# M135A.net
KiCad netlist of a schematic drawn in EAGLE
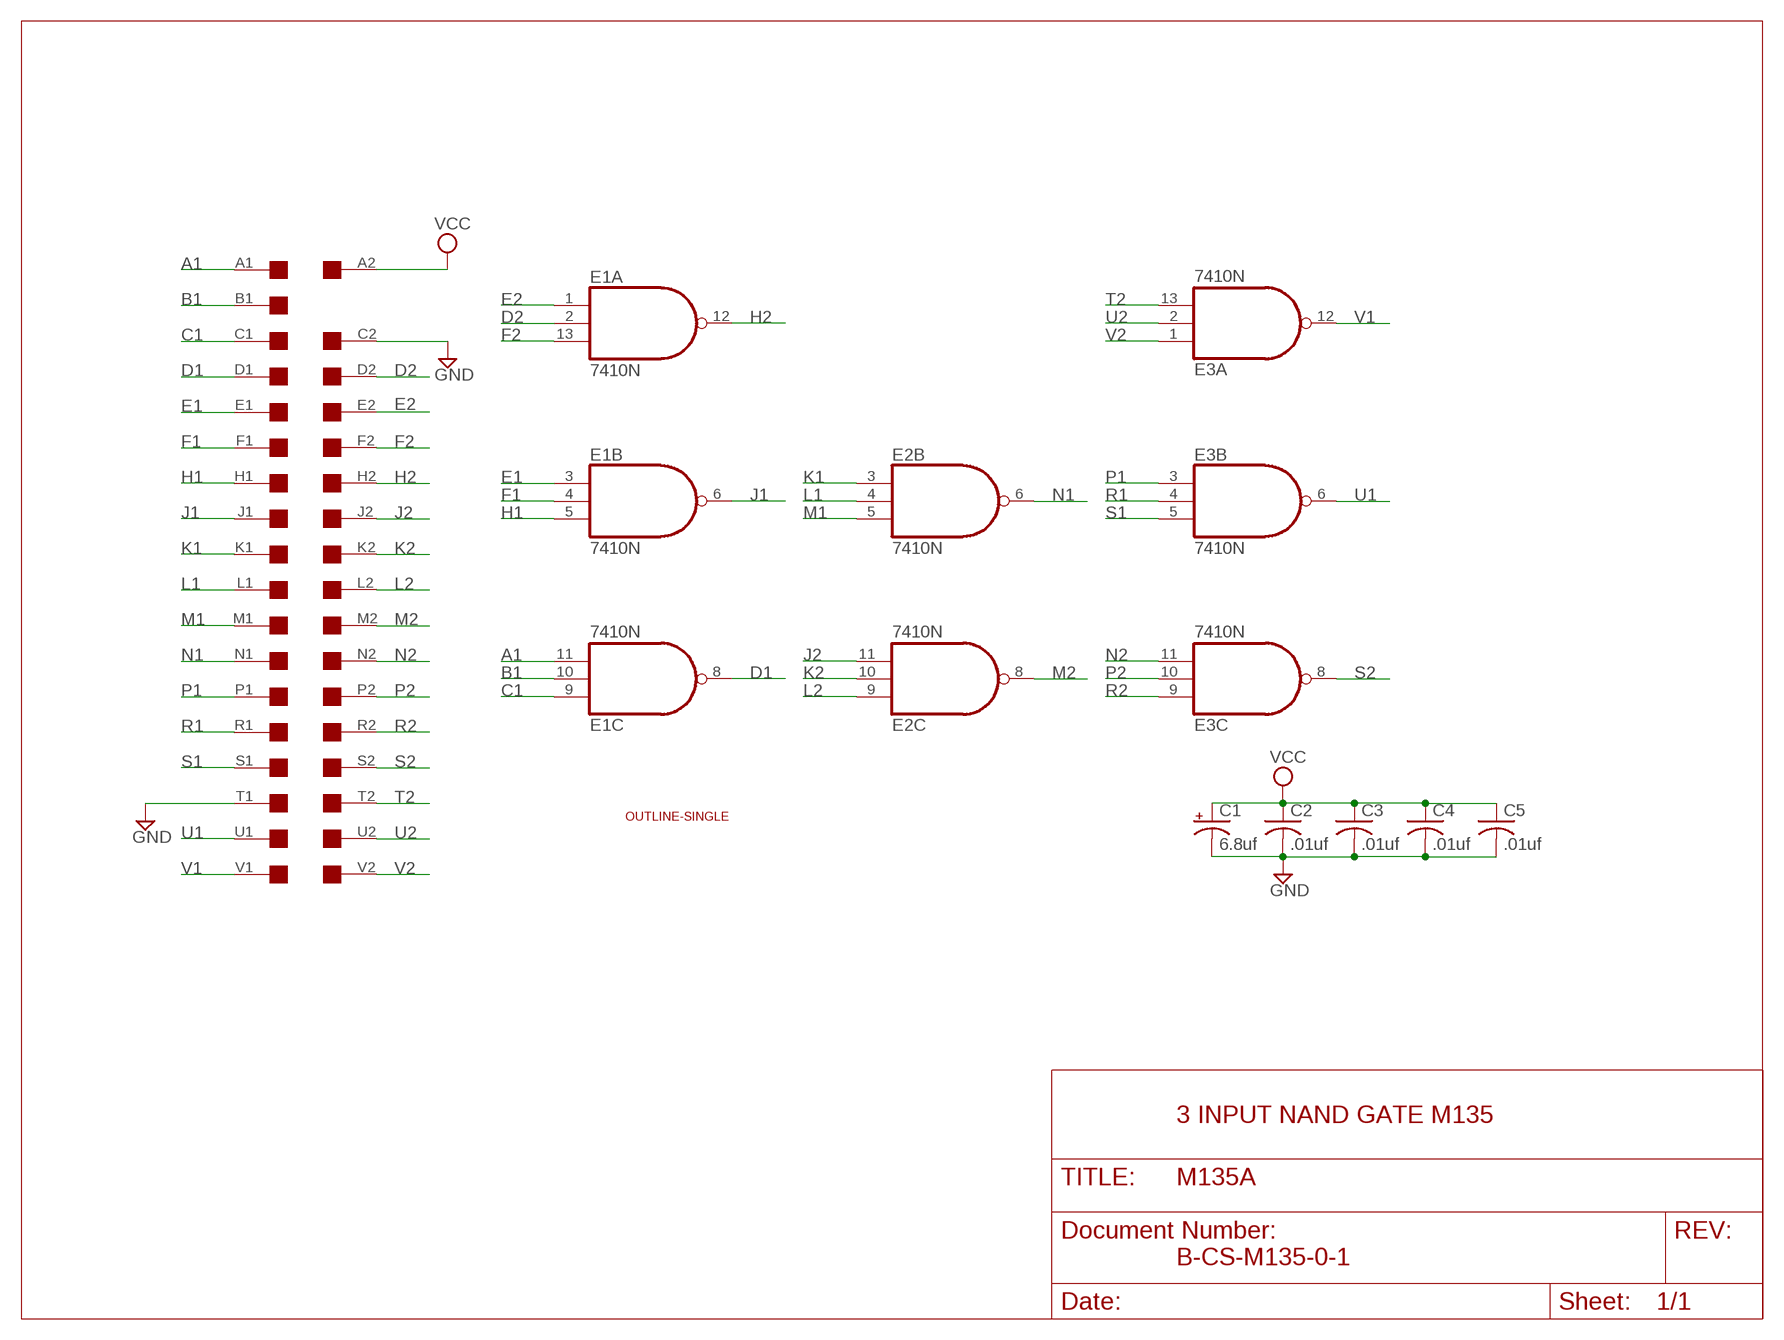
[diagram p0: schematic, sheet 1]

(export (version "E")
  (design (tool "Eeschema 10.0.6"))
  (components
    (comp (ref "C1")
      (value "6.8uf")
      (footprint "eagle-import:E15-5")
      (libsource (lib "eagle-import") (part "CPOL-USE15-5AXIAL"))
    )
    (comp (ref "C2")
      (value ".01uf")
      (footprint "eagle-import:C050-025X075")
      (libsource (lib "eagle-import") (part "C-US050-025X075"))
    )
    (comp (ref "C3")
      (value ".01uf")
      (footprint "eagle-import:C050-025X075")
      (libsource (lib "eagle-import") (part "C-US050-025X075"))
    )
    (comp (ref "C4")
      (value ".01uf")
      (footprint "eagle-import:C050-025X075")
      (libsource (lib "eagle-import") (part "C-US050-025X075"))
    )
    (comp (ref "C5")
      (value ".01uf")
      (footprint "eagle-import:C050-025X075")
      (libsource (lib "eagle-import") (part "C-US050-025X075"))
    )
    (comp (ref "E1")
      (value "7410N")
      (footprint "eagle-import:DIL14")
      (libsource (lib "eagle-import") (part "7410N"))
    )
    (comp (ref "E2")
      (value "7410N")
      (footprint "eagle-import:DIL14")
      (libsource (lib "eagle-import") (part "7410N"))
    )
    (comp (ref "E3")
      (value "7410N")
      (footprint "eagle-import:DIL14")
      (libsource (lib "eagle-import") (part "7410N"))
    )
    (comp (ref "U$1")
      (value "SINGLE")
      (footprint "eagle-import:EDGE-CON2")
      (libsource (lib "eagle-import") (part "SINGLE"))
    )
    (comp (ref "U$4")
      (value "OUTLINE-SINGLE")
      (footprint "eagle-import:SINGLE")
      (libsource (lib "eagle-import") (part "OUTLINE-SINGLE"))
    )
  )
  (nets
    (net (code "1") (name "/A1") (class "Default")
      (node (ref "E1") (pin "11") (pinfunction "I2_11") (pintype "input"))
      (node (ref "U$1") (pin "A1") (pinfunction "1_A1") (pintype "bidirectional"))
    )
    (net (code "2") (name "/B1") (class "Default")
      (node (ref "E1") (pin "10") (pinfunction "I1_10") (pintype "input"))
      (node (ref "U$1") (pin "B1") (pinfunction "1_B1") (pintype "bidirectional"))
    )
    (net (code "3") (name "/C1") (class "Default")
      (node (ref "E1") (pin "9") (pinfunction "I0_9") (pintype "input"))
      (node (ref "U$1") (pin "C1") (pinfunction "1_C1") (pintype "bidirectional"))
    )
    (net (code "4") (name "/D1") (class "Default")
      (node (ref "E1") (pin "8") (pinfunction "O_8") (pintype "output"))
      (node (ref "U$1") (pin "D1") (pinfunction "1_D1") (pintype "bidirectional"))
    )
    (net (code "5") (name "/D2") (class "Default")
      (node (ref "E1") (pin "2") (pinfunction "I1_2") (pintype "input"))
      (node (ref "U$1") (pin "D2") (pinfunction "1_D2") (pintype "bidirectional"))
    )
    (net (code "6") (name "/E1") (class "Default")
      (node (ref "E1") (pin "3") (pinfunction "I0_3") (pintype "input"))
      (node (ref "U$1") (pin "E1") (pinfunction "1_E1") (pintype "bidirectional"))
    )
    (net (code "7") (name "/E2") (class "Default")
      (node (ref "E1") (pin "1") (pinfunction "I0_1") (pintype "input"))
      (node (ref "U$1") (pin "E2") (pinfunction "1_E2") (pintype "bidirectional"))
    )
    (net (code "8") (name "/F1") (class "Default")
      (node (ref "E1") (pin "4") (pinfunction "I1_4") (pintype "input"))
      (node (ref "U$1") (pin "F1") (pinfunction "1_F1") (pintype "bidirectional"))
    )
    (net (code "9") (name "/F2") (class "Default")
      (node (ref "E1") (pin "13") (pinfunction "I2_13") (pintype "input"))
      (node (ref "U$1") (pin "F2") (pinfunction "1_F2") (pintype "bidirectional"))
    )
    (net (code "10") (name "/H1") (class "Default")
      (node (ref "E1") (pin "5") (pinfunction "I2_5") (pintype "input"))
      (node (ref "U$1") (pin "H1") (pinfunction "1_H1") (pintype "bidirectional"))
    )
    (net (code "11") (name "/H2") (class "Default")
      (node (ref "E1") (pin "12") (pinfunction "O_12") (pintype "output"))
      (node (ref "U$1") (pin "H2") (pinfunction "1_H2") (pintype "bidirectional"))
    )
    (net (code "12") (name "/J1") (class "Default")
      (node (ref "E1") (pin "6") (pinfunction "O_6") (pintype "output"))
      (node (ref "U$1") (pin "J1") (pinfunction "1_J1") (pintype "bidirectional"))
    )
    (net (code "13") (name "/J2") (class "Default")
      (node (ref "E2") (pin "11") (pinfunction "I2_11") (pintype "input"))
      (node (ref "U$1") (pin "J2") (pinfunction "1_J2") (pintype "bidirectional"))
    )
    (net (code "14") (name "/K1") (class "Default")
      (node (ref "E2") (pin "3") (pinfunction "I0_3") (pintype "input"))
      (node (ref "U$1") (pin "K1") (pinfunction "1_K1") (pintype "bidirectional"))
    )
    (net (code "15") (name "/K2") (class "Default")
      (node (ref "E2") (pin "10") (pinfunction "I1_10") (pintype "input"))
      (node (ref "U$1") (pin "K2") (pinfunction "1_K2") (pintype "bidirectional"))
    )
    (net (code "16") (name "/L1") (class "Default")
      (node (ref "E2") (pin "4") (pinfunction "I1_4") (pintype "input"))
      (node (ref "U$1") (pin "L1") (pinfunction "1_L1") (pintype "bidirectional"))
    )
    (net (code "17") (name "/L2") (class "Default")
      (node (ref "E2") (pin "9") (pinfunction "I0_9") (pintype "input"))
      (node (ref "U$1") (pin "L2") (pinfunction "1_L2") (pintype "bidirectional"))
    )
    (net (code "18") (name "/M1") (class "Default")
      (node (ref "E2") (pin "5") (pinfunction "I2_5") (pintype "input"))
      (node (ref "U$1") (pin "M1") (pinfunction "1_M1") (pintype "bidirectional"))
    )
    (net (code "19") (name "/M2") (class "Default")
      (node (ref "E2") (pin "8") (pinfunction "O_8") (pintype "output"))
      (node (ref "U$1") (pin "M2") (pinfunction "1_M2") (pintype "bidirectional"))
    )
    (net (code "20") (name "/N1") (class "Default")
      (node (ref "E2") (pin "6") (pinfunction "O_6") (pintype "output"))
      (node (ref "U$1") (pin "N1") (pinfunction "1_N1") (pintype "bidirectional"))
    )
    (net (code "21") (name "/N2") (class "Default")
      (node (ref "E3") (pin "11") (pinfunction "I2_11") (pintype "input"))
      (node (ref "U$1") (pin "N2") (pinfunction "1_N2") (pintype "bidirectional"))
    )
    (net (code "22") (name "/P1") (class "Default")
      (node (ref "E3") (pin "3") (pinfunction "I0_3") (pintype "input"))
      (node (ref "U$1") (pin "P1") (pinfunction "1_P1") (pintype "bidirectional"))
    )
    (net (code "23") (name "/P2") (class "Default")
      (node (ref "E3") (pin "10") (pinfunction "I1_10") (pintype "input"))
      (node (ref "U$1") (pin "P2") (pinfunction "1_P2") (pintype "bidirectional"))
    )
    (net (code "24") (name "/R1") (class "Default")
      (node (ref "E3") (pin "4") (pinfunction "I1_4") (pintype "input"))
      (node (ref "U$1") (pin "R1") (pinfunction "1_R1") (pintype "bidirectional"))
    )
    (net (code "25") (name "/R2") (class "Default")
      (node (ref "E3") (pin "9") (pinfunction "I0_9") (pintype "input"))
      (node (ref "U$1") (pin "R2") (pinfunction "1_R2") (pintype "bidirectional"))
    )
    (net (code "26") (name "/S1") (class "Default")
      (node (ref "E3") (pin "5") (pinfunction "I2_5") (pintype "input"))
      (node (ref "U$1") (pin "S1") (pinfunction "1_S1") (pintype "bidirectional"))
    )
    (net (code "27") (name "/S2") (class "Default")
      (node (ref "E3") (pin "8") (pinfunction "O_8") (pintype "output"))
      (node (ref "U$1") (pin "S2") (pinfunction "1_S2") (pintype "bidirectional"))
    )
    (net (code "28") (name "/T2") (class "Default")
      (node (ref "E3") (pin "13") (pinfunction "I2_13") (pintype "input"))
      (node (ref "U$1") (pin "T2") (pinfunction "1_T2") (pintype "bidirectional"))
    )
    (net (code "29") (name "/U1") (class "Default")
      (node (ref "E3") (pin "6") (pinfunction "O_6") (pintype "output"))
      (node (ref "U$1") (pin "U1") (pinfunction "1_U1") (pintype "bidirectional"))
    )
    (net (code "30") (name "/U2") (class "Default")
      (node (ref "E3") (pin "2") (pinfunction "I1_2") (pintype "input"))
      (node (ref "U$1") (pin "U2") (pinfunction "1_U2") (pintype "bidirectional"))
    )
    (net (code "31") (name "/V1") (class "Default")
      (node (ref "E3") (pin "12") (pinfunction "O_12") (pintype "output"))
      (node (ref "U$1") (pin "V1") (pinfunction "1_V1") (pintype "bidirectional"))
    )
    (net (code "32") (name "/V2") (class "Default")
      (node (ref "E3") (pin "1") (pinfunction "I0_1") (pintype "input"))
      (node (ref "U$1") (pin "V2") (pinfunction "1_V2") (pintype "bidirectional"))
    )
    (net (code "33") (name "GND") (class "Default")
      (node (ref "C1") (pin "-") (pinfunction "-_-") (pintype "passive"))
      (node (ref "C2") (pin "2") (pinfunction "2_2") (pintype "passive"))
      (node (ref "C3") (pin "2") (pinfunction "2_2") (pintype "passive"))
      (node (ref "C4") (pin "2") (pinfunction "2_2") (pintype "passive"))
      (node (ref "C5") (pin "2") (pinfunction "2_2") (pintype "passive"))
      (node (ref "U$1") (pin "C2") (pinfunction "1_C2") (pintype "bidirectional"))
      (node (ref "U$1") (pin "T1") (pinfunction "1_T1") (pintype "bidirectional"))
    )
    (net (code "34") (name "VCC") (class "Default")
      (node (ref "C1") (pin "+") (pinfunction "+_+") (pintype "passive"))
      (node (ref "C2") (pin "1") (pinfunction "1_1") (pintype "passive"))
      (node (ref "C3") (pin "1") (pinfunction "1_1") (pintype "passive"))
      (node (ref "C4") (pin "1") (pinfunction "1_1") (pintype "passive"))
      (node (ref "C5") (pin "1") (pinfunction "1_1") (pintype "passive"))
      (node (ref "U$1") (pin "A2") (pinfunction "1_A2") (pintype "bidirectional"))
    )
  )
)
